# therma.net
KiCad netlist of a schematic drawn in EAGLE
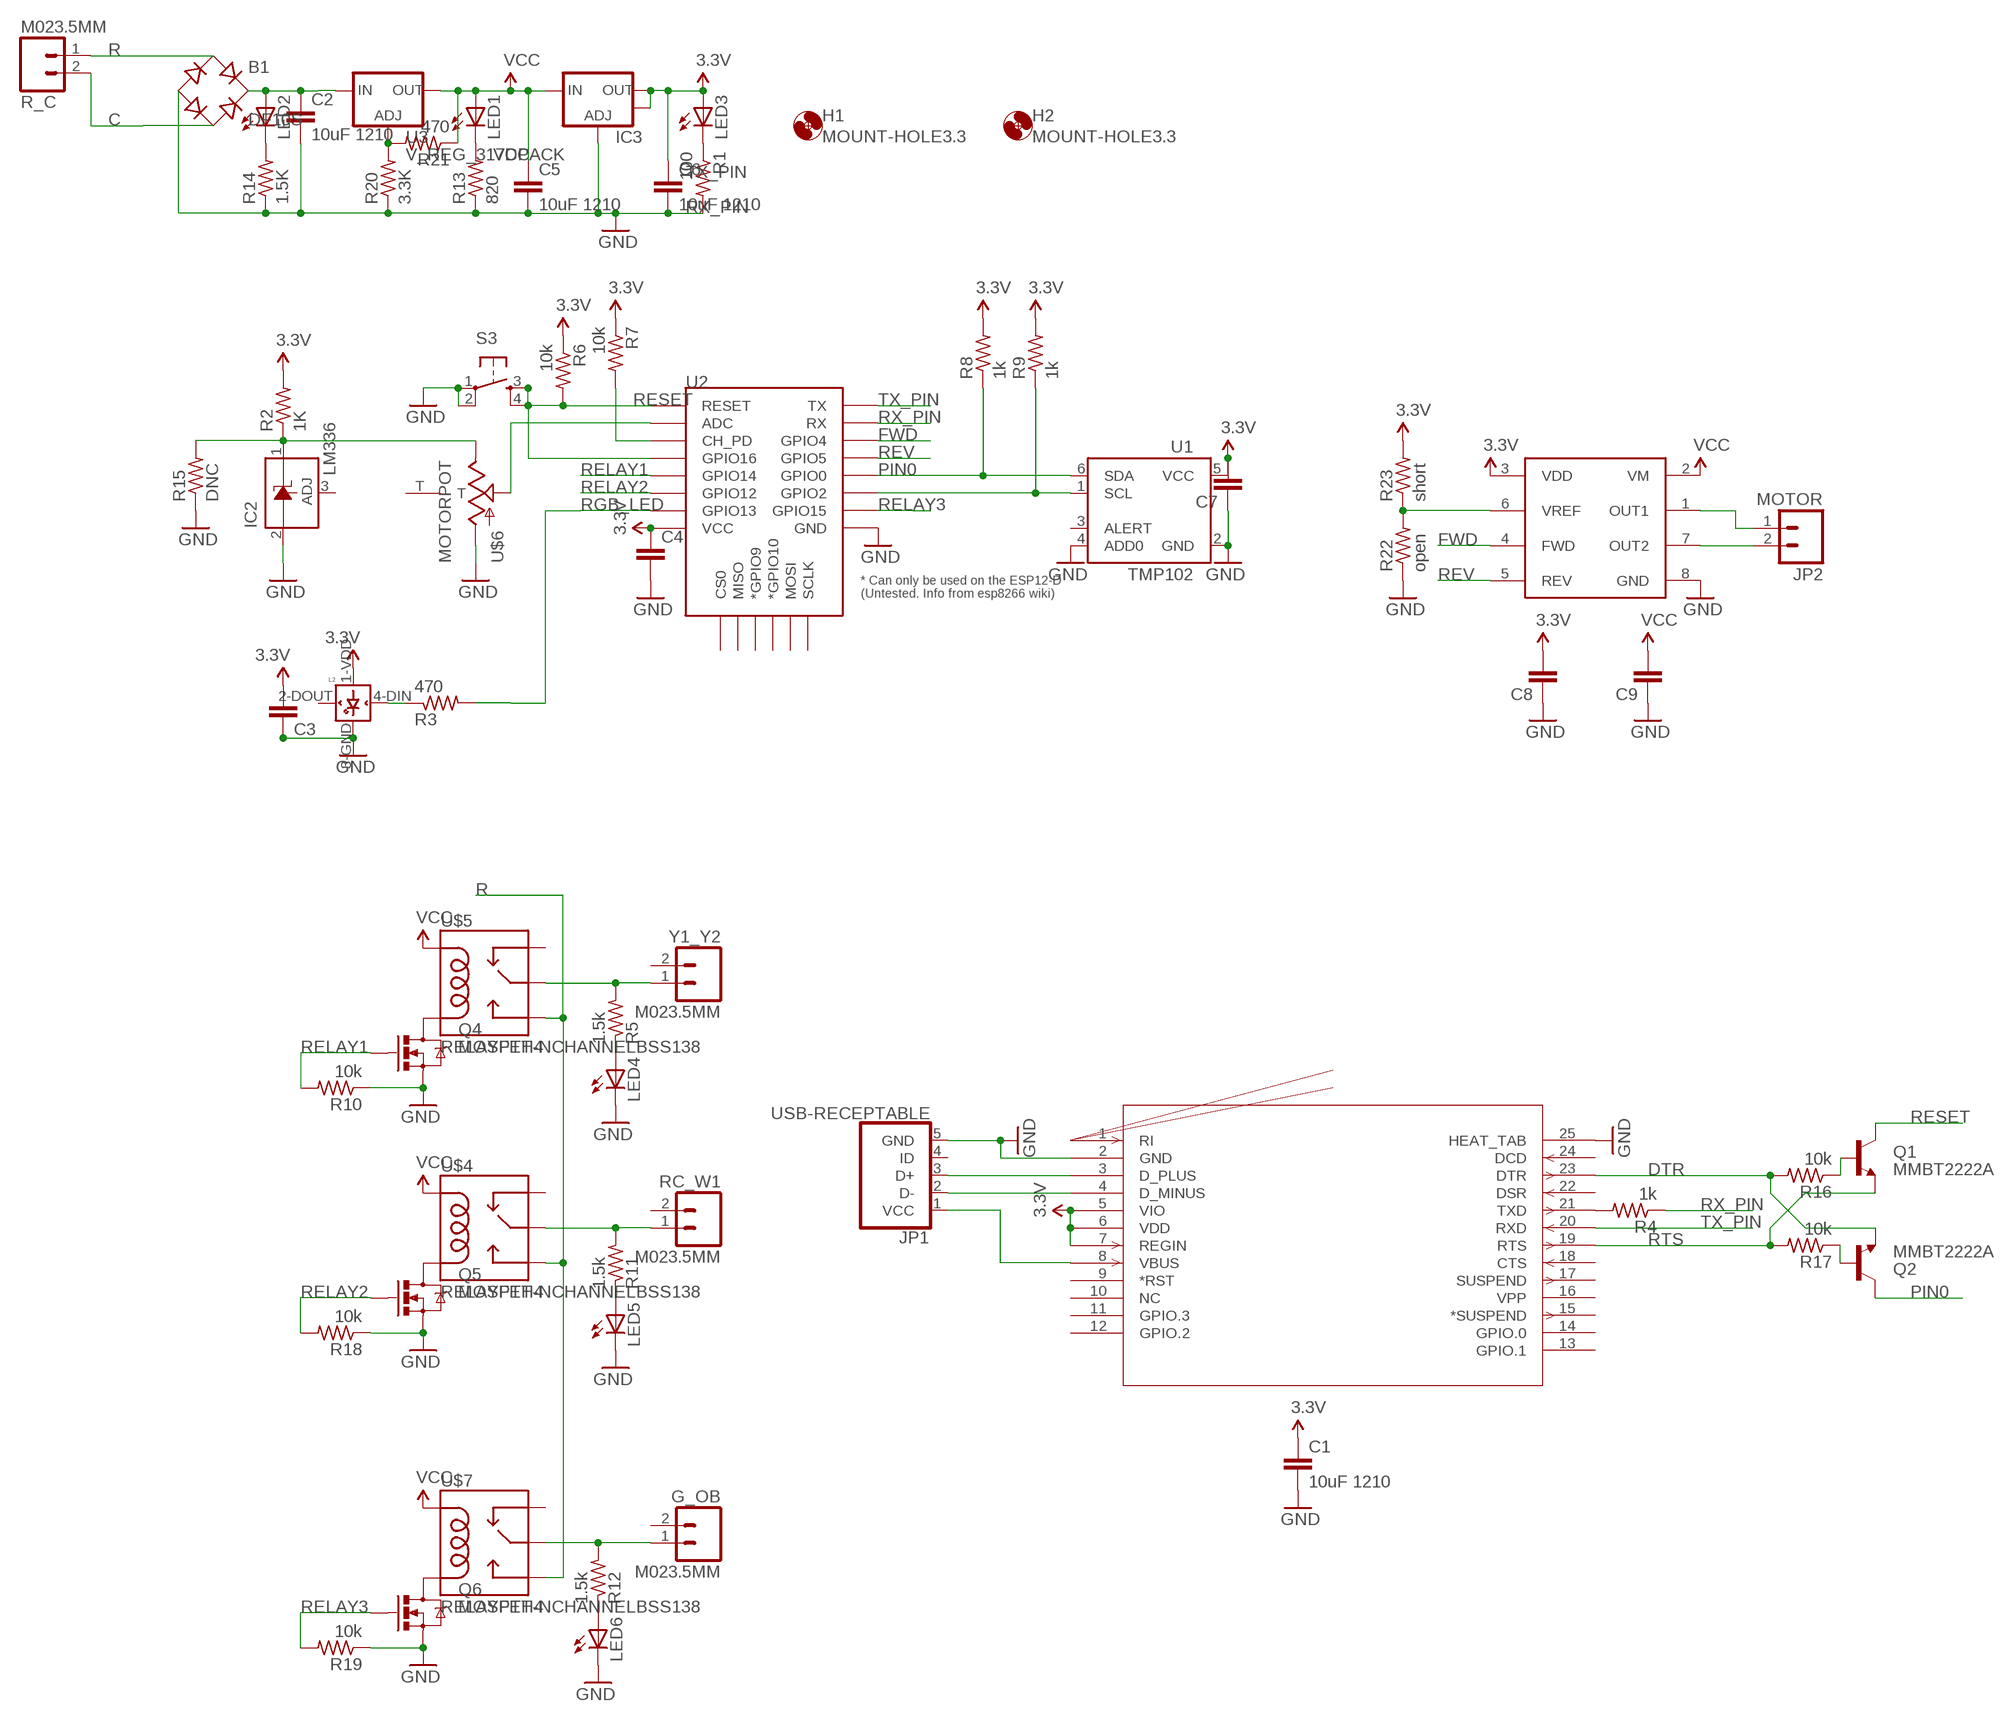
[diagram p0: schematic, sheet 1]

(export (version "E")
  (design (tool "Eeschema 10.0.6"))
  (components
    (comp (ref "B1")
      (value "DF10S")
      (footprint "eagle-import:DFS")
      (libsource (lib "eagle-import") (part "DFS10"))
    )
    (comp (ref "C1")
      (value "10uF 1210")
      (footprint "eagle-import:1210")
      (fields (field (name "PROD_ID") "CAP-09824"))
      (libsource (lib "eagle-import") (part "10UF50V20%(1210)"))
    )
    (comp (ref "C2")
      (value "10uF 1210")
      (footprint "eagle-import:1210")
      (fields (field (name "PROD_ID") "CAP-09824"))
      (libsource (lib "eagle-import") (part "10UF50V20%(1210)"))
    )
    (comp (ref "C3")
      (value "CAP0603-CAP")
      (footprint "eagle-import:0603-CAP")
      (libsource (lib "eagle-import") (part "CAP0603-CAP"))
    )
    (comp (ref "C4")
      (value "CAP0603-CAP")
      (footprint "eagle-import:0603-CAP")
      (libsource (lib "eagle-import") (part "CAP0603-CAP"))
    )
    (comp (ref "C5")
      (value "10uF 1210")
      (footprint "eagle-import:1210")
      (libsource (lib "eagle-import") (part "10UF50V20%(1210)"))
    )
    (comp (ref "C6")
      (value "10uF 1210")
      (footprint "eagle-import:1210")
      (fields (field (name "PROD_ID") "CAP-09824"))
      (libsource (lib "eagle-import") (part "10UF50V20%(1210)"))
    )
    (comp (ref "C7")
      (value "CAP0603-CAP")
      (footprint "eagle-import:0603-CAP")
      (libsource (lib "eagle-import") (part "CAP0603-CAP"))
    )
    (comp (ref "C8")
      (value "CAP0603-CAP")
      (footprint "eagle-import:0603-CAP")
      (libsource (lib "eagle-import") (part "CAP0603-CAP"))
    )
    (comp (ref "C9")
      (value "CAP0603-CAP")
      (footprint "eagle-import:0603-CAP")
      (libsource (lib "eagle-import") (part "CAP0603-CAP"))
    )
    (comp (ref "G_OB")
      (value "M023.5MM")
      (footprint "eagle-import:SCREWTERMINAL-3.5MM-2")
      (libsource (lib "eagle-import") (part "M023.5MM"))
    )
    (comp (ref "H1")
      (value "MOUNT-HOLE3.3")
      (footprint "eagle-import:3,3")
      (libsource (lib "eagle-import") (part "MOUNT-HOLE3.3"))
    )
    (comp (ref "H2")
      (value "MOUNT-HOLE3.3")
      (footprint "eagle-import:3,3")
      (libsource (lib "eagle-import") (part "MOUNT-HOLE3.3"))
    )
    (comp (ref "IC2")
      (value "LM336")
      (footprint "eagle-import:SOT23-3")
      (libsource (lib "eagle-import") (part "LM336"))
    )
    (comp (ref "IC3")
      (value "V_REG_LM1117SOT223")
      (footprint "eagle-import:SOT223")
      (libsource (lib "eagle-import") (part "V_REG_LM1117SOT223"))
    )
    (comp (ref "JP1")
      (value "USB-RECEPTABLE")
      (footprint "eagle-import:FCI-10103594-0001LF")
      (libsource (lib "eagle-import") (part "USB-RECEPTABLE"))
    )
    (comp (ref "JP2")
      (value "MOTOR")
      (footprint "eagle-import:1X02")
      (libsource (lib "eagle-import") (part "M02PTH"))
    )
    (comp (ref "L2")
      (value "WS2812B")
      (footprint "eagle-import:WS2812B")
      (libsource (lib "eagle-import") (part "WS2812B"))
    )
    (comp (ref "LED1")
      (value "LEDCHIPLED_1206")
      (footprint "eagle-import:CHIPLED_1206")
      (libsource (lib "eagle-import") (part "LEDCHIPLED_1206"))
    )
    (comp (ref "LED2")
      (value "LEDCHIPLED_1206")
      (footprint "eagle-import:CHIPLED_1206")
      (libsource (lib "eagle-import") (part "LEDCHIPLED_1206"))
    )
    (comp (ref "LED3")
      (value "LEDCHIPLED_1206")
      (footprint "eagle-import:CHIPLED_1206")
      (libsource (lib "eagle-import") (part "LEDCHIPLED_1206"))
    )
    (comp (ref "LED4")
      (value "LEDCHIPLED_1206")
      (footprint "eagle-import:CHIPLED_1206")
      (libsource (lib "eagle-import") (part "LEDCHIPLED_1206"))
    )
    (comp (ref "LED5")
      (value "LEDCHIPLED_1206")
      (footprint "eagle-import:CHIPLED_1206")
      (libsource (lib "eagle-import") (part "LEDCHIPLED_1206"))
    )
    (comp (ref "LED6")
      (value "LEDCHIPLED_1206")
      (footprint "eagle-import:CHIPLED_1206")
      (libsource (lib "eagle-import") (part "LEDCHIPLED_1206"))
    )
    (comp (ref "Q1")
      (value "MMBT2222A")
      (footprint "eagle-import:SOT23")
      (libsource (lib "eagle-import") (part "TRANSISTOR_NPNMMBT2222A"))
    )
    (comp (ref "Q2")
      (value "MMBT2222A")
      (footprint "eagle-import:SOT23")
      (libsource (lib "eagle-import") (part "TRANSISTOR_NPNMMBT2222A"))
    )
    (comp (ref "Q4")
      (value "MOSFET-NCHANNELBSS138")
      (footprint "eagle-import:SOT23")
      (libsource (lib "eagle-import") (part "MOSFET-NCHANNELBSS138"))
    )
    (comp (ref "Q5")
      (value "MOSFET-NCHANNELBSS138")
      (footprint "eagle-import:SOT23")
      (libsource (lib "eagle-import") (part "MOSFET-NCHANNELBSS138"))
    )
    (comp (ref "Q6")
      (value "MOSFET-NCHANNELBSS138")
      (footprint "eagle-import:SOT23")
      (libsource (lib "eagle-import") (part "MOSFET-NCHANNELBSS138"))
    )
    (comp (ref "R1")
      (value "100")
      (footprint "eagle-import:R0603")
      (libsource (lib "eagle-import") (part "R-US_R0603"))
    )
    (comp (ref "R2")
      (value "1K")
      (footprint "eagle-import:R0603")
      (libsource (lib "eagle-import") (part "R-US_R0603"))
    )
    (comp (ref "R3")
      (value "470")
      (footprint "eagle-import:R0603")
      (libsource (lib "eagle-import") (part "R-US_R0603"))
    )
    (comp (ref "R4")
      (value "1k")
      (footprint "eagle-import:R0603")
      (libsource (lib "eagle-import") (part "R-US_R0603"))
    )
    (comp (ref "R5")
      (value "1.5k")
      (footprint "eagle-import:R0603")
      (libsource (lib "eagle-import") (part "R-US_R0603"))
    )
    (comp (ref "R6")
      (value "10k")
      (footprint "eagle-import:R0603")
      (libsource (lib "eagle-import") (part "R-US_R0603"))
    )
    (comp (ref "R7")
      (value "10k")
      (footprint "eagle-import:R0603")
      (libsource (lib "eagle-import") (part "R-US_R0603"))
    )
    (comp (ref "R8")
      (value "1k")
      (footprint "eagle-import:R0603")
      (libsource (lib "eagle-import") (part "R-US_R0603"))
    )
    (comp (ref "R9")
      (value "1k")
      (footprint "eagle-import:R0603")
      (libsource (lib "eagle-import") (part "R-US_R0603"))
    )
    (comp (ref "R10")
      (value "10k")
      (footprint "eagle-import:R0603")
      (libsource (lib "eagle-import") (part "R-US_R0603"))
    )
    (comp (ref "R11")
      (value "1.5k")
      (footprint "eagle-import:R0603")
      (libsource (lib "eagle-import") (part "R-US_R0603"))
    )
    (comp (ref "R12")
      (value "1.5k")
      (footprint "eagle-import:R0603")
      (libsource (lib "eagle-import") (part "R-US_R0603"))
    )
    (comp (ref "R13")
      (value "820")
      (footprint "eagle-import:R0603")
      (libsource (lib "eagle-import") (part "R-US_R0603"))
    )
    (comp (ref "R14")
      (value "1.5K")
      (footprint "eagle-import:R0603")
      (libsource (lib "eagle-import") (part "R-US_R0603"))
    )
    (comp (ref "R15")
      (value "DNC")
      (footprint "eagle-import:R0603")
      (libsource (lib "eagle-import") (part "R-US_R0603"))
    )
    (comp (ref "R16")
      (value "10k")
      (footprint "eagle-import:R0603")
      (libsource (lib "eagle-import") (part "R-US_R0603"))
    )
    (comp (ref "R17")
      (value "10k")
      (footprint "eagle-import:R0603")
      (libsource (lib "eagle-import") (part "R-US_R0603"))
    )
    (comp (ref "R18")
      (value "10k")
      (footprint "eagle-import:R0603")
      (libsource (lib "eagle-import") (part "R-US_R0603"))
    )
    (comp (ref "R19")
      (value "10k")
      (footprint "eagle-import:R0603")
      (libsource (lib "eagle-import") (part "R-US_R0603"))
    )
    (comp (ref "R20")
      (value "3.3K")
      (footprint "eagle-import:R0603")
      (libsource (lib "eagle-import") (part "R-US_R0603"))
    )
    (comp (ref "R21")
      (value "470")
      (footprint "eagle-import:R0603")
      (libsource (lib "eagle-import") (part "R-US_R0603"))
    )
    (comp (ref "R22")
      (value "open")
      (footprint "eagle-import:R0603")
      (libsource (lib "eagle-import") (part "R-US_R0603"))
    )
    (comp (ref "R23")
      (value "short")
      (footprint "eagle-import:R0603")
      (libsource (lib "eagle-import") (part "R-US_R0603"))
    )
    (comp (ref "RC_W1")
      (value "M023.5MM")
      (footprint "eagle-import:SCREWTERMINAL-3.5MM-2")
      (libsource (lib "eagle-import") (part "M023.5MM"))
    )
    (comp (ref "R_C")
      (value "M023.5MM")
      (footprint "eagle-import:SCREWTERMINAL-3.5MM-2")
      (libsource (lib "eagle-import") (part "M023.5MM"))
    )
    (comp (ref "S3")
      (value "TAC_SWITCHSMD")
      (footprint "eagle-import:TACTILE_SWITCH_SMD")
      (libsource (lib "eagle-import") (part "TAC_SWITCHSMD"))
    )
    (comp (ref "U$1")
      (value "ZXBM5210SOIC")
      (footprint "eagle-import:SOIC8")
      (libsource (lib "eagle-import") (part "ZXBM5210SOIC"))
    )
    (comp (ref "U$4")
      (value "RELAYPTH4")
      (footprint "eagle-import:RELAY-JZC")
      (libsource (lib "eagle-import") (part "RELAYPTH4"))
    )
    (comp (ref "U$5")
      (value "RELAYPTH4")
      (footprint "eagle-import:RELAY-JZC")
      (libsource (lib "eagle-import") (part "RELAYPTH4"))
    )
    (comp (ref "U$6")
      (value "MOTORPOT")
      (footprint "eagle-import:MOTORIZEDPOT")
      (libsource (lib "eagle-import") (part "MOTORPOT"))
    )
    (comp (ref "U$7")
      (value "RELAYPTH4")
      (footprint "eagle-import:RELAY-JZC")
      (libsource (lib "eagle-import") (part "RELAYPTH4"))
    )
    (comp (ref "U$8")
      (value "CP2104-GM")
      (footprint "eagle-import:QFN24_4X4")
      (libsource (lib "eagle-import") (part "CP2104-GM"))
    )
    (comp (ref "U1")
      (value "TMP102")
      (footprint "eagle-import:SOT563")
      (libsource (lib "eagle-import") (part "TMP102"))
    )
    (comp (ref "U2")
      (value "ESP12ESMD")
      (footprint "eagle-import:ESP12E-SMD")
      (libsource (lib "eagle-import") (part "ESP12ESMD"))
    )
    (comp (ref "U3")
      (value "V_REG_317DPACK")
      (footprint "eagle-import:V-REG_DPACK")
      (libsource (lib "eagle-import") (part "V_REG_317DPACK"))
    )
    (comp (ref "Y1_Y2")
      (value "M023.5MM")
      (footprint "eagle-import:SCREWTERMINAL-3.5MM-2")
      (libsource (lib "eagle-import") (part "M023.5MM"))
    )
  )
  (nets
    (net (code "1") (name "/C") (class "Default")
      (node (ref "B1") (pin "AC2") (pinfunction "AC2_AC2") (pintype "passive"))
      (node (ref "R_C") (pin "2") (pinfunction "2_2") (pintype "passive"))
    )
    (net (code "2") (name "/DTR") (class "Default")
      (node (ref "Q2") (pin "2") (pinfunction "E_2") (pintype "passive"))
      (node (ref "R16") (pin "2") (pinfunction "2_2") (pintype "passive"))
      (node (ref "U$8") (pin "23") (pinfunction "DTR_23") (pintype "output"))
    )
    (net (code "3") (name "/FWD") (class "Default")
      (node (ref "U$1") (pin "4") (pinfunction "FWD_4") (pintype "bidirectional"))
      (node (ref "U2") (pin "GPIO4") (pinfunction "GPIO4_GPIO4") (pintype "bidirectional"))
    )
    (net (code "4") (name "/PIN0") (class "Default")
      (node (ref "Q2") (pin "3") (pinfunction "C_3") (pintype "passive"))
      (node (ref "R8") (pin "1") (pinfunction "1_1") (pintype "passive"))
      (node (ref "U1") (pin "6") (pinfunction "SDA_6") (pintype "bidirectional"))
      (node (ref "U2") (pin "GPIO0") (pinfunction "GPIO0_GPIO0") (pintype "bidirectional"))
    )
    (net (code "5") (name "/R") (class "Default")
      (node (ref "B1") (pin "AC1") (pinfunction "AC1_AC1") (pintype "passive"))
      (node (ref "R_C") (pin "1") (pinfunction "1_1") (pintype "passive"))
      (node (ref "U$4") (pin "3") (pinfunction "NO_3") (pintype "bidirectional"))
      (node (ref "U$5") (pin "3") (pinfunction "NO_3") (pintype "bidirectional"))
      (node (ref "U$7") (pin "3") (pinfunction "NO_3") (pintype "bidirectional"))
    )
    (net (code "6") (name "/RELAY1") (class "Default")
      (node (ref "Q4") (pin "1") (pinfunction "G_1") (pintype "passive"))
      (node (ref "R10") (pin "2") (pinfunction "2_2") (pintype "passive"))
      (node (ref "U2") (pin "GPIO14") (pinfunction "GPIO14_GPIO14") (pintype "bidirectional"))
    )
    (net (code "7") (name "/RELAY2") (class "Default")
      (node (ref "Q5") (pin "1") (pinfunction "G_1") (pintype "passive"))
      (node (ref "R18") (pin "2") (pinfunction "2_2") (pintype "passive"))
      (node (ref "U2") (pin "GPIO12") (pinfunction "GPIO12_GPIO12") (pintype "bidirectional"))
    )
    (net (code "8") (name "/RELAY3") (class "Default")
      (node (ref "Q6") (pin "1") (pinfunction "G_1") (pintype "passive"))
      (node (ref "R19") (pin "2") (pinfunction "2_2") (pintype "passive"))
      (node (ref "U2") (pin "GPIO15") (pinfunction "GPIO15_GPIO15") (pintype "bidirectional"))
    )
    (net (code "9") (name "/RESET") (class "Default")
      (node (ref "Q1") (pin "3") (pinfunction "C_3") (pintype "passive"))
      (node (ref "R6") (pin "2") (pinfunction "2_2") (pintype "passive"))
      (node (ref "S3") (pin "3") (pinfunction "3_3") (pintype "passive"))
      (node (ref "S3") (pin "4") (pinfunction "4_4") (pintype "passive"))
      (node (ref "U2") (pin "GPIO16") (pinfunction "GPIO16_GPIO16") (pintype "bidirectional"))
      (node (ref "U2") (pin "RESET") (pinfunction "RESET_RESET") (pintype "bidirectional"))
    )
    (net (code "10") (name "/REV") (class "Default")
      (node (ref "U$1") (pin "5") (pinfunction "REV_5") (pintype "bidirectional"))
      (node (ref "U2") (pin "GPIO5") (pinfunction "GPIO5_GPIO5") (pintype "bidirectional"))
    )
    (net (code "11") (name "/RGB_LED") (class "Default")
      (node (ref "R3") (pin "2") (pinfunction "2_2") (pintype "passive"))
      (node (ref "U2") (pin "GPIO13") (pinfunction "GPIO13_GPIO13") (pintype "bidirectional"))
    )
    (net (code "12") (name "/RTS") (class "Default")
      (node (ref "Q1") (pin "2") (pinfunction "E_2") (pintype "passive"))
      (node (ref "R17") (pin "2") (pinfunction "2_2") (pintype "passive"))
      (node (ref "U$8") (pin "19") (pinfunction "RTS_19") (pintype "output"))
    )
    (net (code "13") (name "/RX_PIN") (class "Default")
      (node (ref "R4") (pin "1") (pinfunction "1_1") (pintype "passive"))
      (node (ref "U2") (pin "RXD0") (pinfunction "RX_RXD0") (pintype "bidirectional"))
    )
    (net (code "14") (name "/TX_PIN") (class "Default")
      (node (ref "U$8") (pin "20") (pinfunction "RXD_20") (pintype "input"))
      (node (ref "U2") (pin "TXD0") (pinfunction "TX_TXD0") (pintype "bidirectional"))
    )
    (net (code "15") (name "3.3V") (class "Default")
      (node (ref "C1") (pin "1") (pinfunction "1_1") (pintype "passive"))
      (node (ref "C3") (pin "2") (pinfunction "2_2") (pintype "passive"))
      (node (ref "C4") (pin "1") (pinfunction "1_1") (pintype "passive"))
      (node (ref "C6") (pin "1") (pinfunction "1_1") (pintype "passive"))
      (node (ref "C7") (pin "2") (pinfunction "2_2") (pintype "passive"))
      (node (ref "C8") (pin "2") (pinfunction "2_2") (pintype "passive"))
      (node (ref "IC3") (pin "2") (pinfunction "OUT_2") (pintype "output"))
      (node (ref "IC3") (pin "4") (pinfunction "OUT_4") (pintype "output"))
      (node (ref "L2") (pin "1-VDD") (pinfunction "VDD_1-VDD") (pintype "bidirectional"))
      (node (ref "LED3") (pin "A") (pinfunction "A_A") (pintype "passive"))
      (node (ref "R2") (pin "2") (pinfunction "2_2") (pintype "passive"))
      (node (ref "R23") (pin "2") (pinfunction "2_2") (pintype "passive"))
      (node (ref "R6") (pin "1") (pinfunction "1_1") (pintype "passive"))
      (node (ref "R7") (pin "1") (pinfunction "1_1") (pintype "passive"))
      (node (ref "R8") (pin "2") (pinfunction "2_2") (pintype "passive"))
      (node (ref "R9") (pin "2") (pinfunction "2_2") (pintype "passive"))
      (node (ref "U$1") (pin "3") (pinfunction "VDD_3") (pintype "bidirectional"))
      (node (ref "U$8") (pin "5") (pinfunction "VIO_5") (pintype "power_in"))
      (node (ref "U$8") (pin "6") (pinfunction "VDD_6") (pintype "power_in"))
      (node (ref "U$8") (pin "7") (pinfunction "REGIN_7") (pintype "input"))
      (node (ref "U1") (pin "5") (pinfunction "VCC_5") (pintype "bidirectional"))
      (node (ref "U2") (pin "VCC") (pinfunction "VCC_VCC") (pintype "bidirectional"))
    )
    (net (code "16") (name "GND") (class "Default")
      (node (ref "B1") (pin "-") (pinfunction "-_-") (pintype "passive"))
      (node (ref "C1") (pin "2") (pinfunction "2_2") (pintype "passive"))
      (node (ref "C2") (pin "2") (pinfunction "2_2") (pintype "passive"))
      (node (ref "C3") (pin "1") (pinfunction "1_1") (pintype "passive"))
      (node (ref "C4") (pin "2") (pinfunction "2_2") (pintype "passive"))
      (node (ref "C5") (pin "2") (pinfunction "2_2") (pintype "passive"))
      (node (ref "C6") (pin "2") (pinfunction "2_2") (pintype "passive"))
      (node (ref "C7") (pin "1") (pinfunction "1_1") (pintype "passive"))
      (node (ref "C8") (pin "1") (pinfunction "1_1") (pintype "passive"))
      (node (ref "C9") (pin "1") (pinfunction "1_1") (pintype "passive"))
      (node (ref "IC2") (pin "2") (pinfunction "A_2") (pintype "input"))
      (node (ref "IC3") (pin "1") (pinfunction "ADJ_1") (pintype "input"))
      (node (ref "JP1") (pin "5") (pinfunction "GND_5") (pintype "bidirectional"))
      (node (ref "L2") (pin "3-GND") (pinfunction "GND_3-GND") (pintype "bidirectional"))
      (node (ref "LED4") (pin "C") (pinfunction "C_C") (pintype "passive"))
      (node (ref "LED5") (pin "C") (pinfunction "C_C") (pintype "passive"))
      (node (ref "LED6") (pin "C") (pinfunction "C_C") (pintype "passive"))
      (node (ref "Q4") (pin "2") (pinfunction "S_2") (pintype "passive"))
      (node (ref "Q5") (pin "2") (pinfunction "S_2") (pintype "passive"))
      (node (ref "Q6") (pin "2") (pinfunction "S_2") (pintype "passive"))
      (node (ref "R1") (pin "2") (pinfunction "2_2") (pintype "passive"))
      (node (ref "R10") (pin "1") (pinfunction "1_1") (pintype "passive"))
      (node (ref "R13") (pin "1") (pinfunction "1_1") (pintype "passive"))
      (node (ref "R14") (pin "1") (pinfunction "1_1") (pintype "passive"))
      (node (ref "R15") (pin "1") (pinfunction "1_1") (pintype "passive"))
      (node (ref "R18") (pin "1") (pinfunction "1_1") (pintype "passive"))
      (node (ref "R19") (pin "1") (pinfunction "1_1") (pintype "passive"))
      (node (ref "R20") (pin "1") (pinfunction "1_1") (pintype "passive"))
      (node (ref "R22") (pin "1") (pinfunction "1_1") (pintype "passive"))
      (node (ref "S3") (pin "1") (pinfunction "1_1") (pintype "passive"))
      (node (ref "S3") (pin "2") (pinfunction "2_2") (pintype "passive"))
      (node (ref "U$1") (pin "8") (pinfunction "GND_8") (pintype "bidirectional"))
      (node (ref "U$6") (pin "3'") (pinfunction "3_3'") (pintype "passive"))
      (node (ref "U$8") (pin "2") (pinfunction "GND_2") (pintype "power_in"))
      (node (ref "U$8") (pin "25") (pinfunction "HEAT_TAB_25") (pintype "passive"))
      (node (ref "U1") (pin "2") (pinfunction "GND_2") (pintype "bidirectional"))
      (node (ref "U1") (pin "4") (pinfunction "ADD0_4") (pintype "bidirectional"))
      (node (ref "U2") (pin "GND") (pinfunction "GND_GND") (pintype "bidirectional"))
    )
    (net (code "17") (name "Net-(IC2-C)") (class "Default")
      (node (ref "IC2") (pin "1") (pinfunction "C_1") (pintype "passive"))
      (node (ref "R15") (pin "2") (pinfunction "2_2") (pintype "passive"))
      (node (ref "R2") (pin "1") (pinfunction "1_1") (pintype "passive"))
      (node (ref "U$6") (pin "1'") (pinfunction "1_1'") (pintype "passive"))
    )
    (net (code "18") (name "Net-(JP1-D+)") (class "Default")
      (node (ref "JP1") (pin "3") (pinfunction "D+_3") (pintype "bidirectional"))
      (node (ref "U$8") (pin "3") (pinfunction "D_PLUS_3") (pintype "passive"))
    )
    (net (code "19") (name "Net-(JP1-D-)") (class "Default")
      (node (ref "JP1") (pin "2") (pinfunction "D-_2") (pintype "bidirectional"))
      (node (ref "U$8") (pin "4") (pinfunction "D_MINUS_4") (pintype "passive"))
    )
    (net (code "20") (name "Net-(JP1-VCC)") (class "Default")
      (node (ref "JP1") (pin "1") (pinfunction "VCC_1") (pintype "bidirectional"))
      (node (ref "U$8") (pin "8") (pinfunction "VBUS_8") (pintype "input"))
    )
    (net (code "21") (name "Net-(L2-DIN)") (class "Default")
      (node (ref "L2") (pin "4-DIN") (pinfunction "DIN_4-DIN") (pintype "input"))
      (node (ref "R3") (pin "1") (pinfunction "1_1") (pintype "passive"))
    )
    (net (code "22") (name "Net-(LED1-PadC)") (class "Default")
      (node (ref "LED1") (pin "C") (pinfunction "C_C") (pintype "passive"))
      (node (ref "R13") (pin "2") (pinfunction "2_2") (pintype "passive"))
    )
    (net (code "23") (name "Net-(LED2-PadC)") (class "Default")
      (node (ref "LED2") (pin "C") (pinfunction "C_C") (pintype "passive"))
      (node (ref "R14") (pin "2") (pinfunction "2_2") (pintype "passive"))
    )
    (net (code "24") (name "Net-(LED3-PadC)") (class "Default")
      (node (ref "LED3") (pin "C") (pinfunction "C_C") (pintype "passive"))
      (node (ref "R1") (pin "1") (pinfunction "1_1") (pintype "passive"))
    )
    (net (code "25") (name "Net-(LED4-PadA)") (class "Default")
      (node (ref "LED4") (pin "A") (pinfunction "A_A") (pintype "passive"))
      (node (ref "R5") (pin "1") (pinfunction "1_1") (pintype "passive"))
    )
    (net (code "26") (name "Net-(LED5-PadA)") (class "Default")
      (node (ref "LED5") (pin "A") (pinfunction "A_A") (pintype "passive"))
      (node (ref "R11") (pin "1") (pinfunction "1_1") (pintype "passive"))
    )
    (net (code "27") (name "Net-(LED6-PadA)") (class "Default")
      (node (ref "LED6") (pin "A") (pinfunction "A_A") (pintype "passive"))
      (node (ref "R12") (pin "1") (pinfunction "1_1") (pintype "passive"))
    )
    (net (code "28") (name "Net-(Q1-B)") (class "Default")
      (node (ref "Q1") (pin "1") (pinfunction "B_1") (pintype "passive"))
      (node (ref "R16") (pin "1") (pinfunction "1_1") (pintype "passive"))
    )
    (net (code "29") (name "Net-(Q2-B)") (class "Default")
      (node (ref "Q2") (pin "1") (pinfunction "B_1") (pintype "passive"))
      (node (ref "R17") (pin "1") (pinfunction "1_1") (pintype "passive"))
    )
    (net (code "30") (name "Net-(Q4-D)") (class "Default")
      (node (ref "Q4") (pin "3") (pinfunction "D_3") (pintype "passive"))
      (node (ref "U$5") (pin "1") (pinfunction "COIL2_1") (pintype "bidirectional"))
    )
    (net (code "31") (name "Net-(Q5-D)") (class "Default")
      (node (ref "Q5") (pin "3") (pinfunction "D_3") (pintype "passive"))
      (node (ref "U$4") (pin "1") (pinfunction "COIL2_1") (pintype "bidirectional"))
    )
    (net (code "32") (name "Net-(Q6-D)") (class "Default")
      (node (ref "Q6") (pin "3") (pinfunction "D_3") (pintype "passive"))
      (node (ref "U$7") (pin "1") (pinfunction "COIL2_1") (pintype "bidirectional"))
    )
    (net (code "33") (name "Net-(R7-Pad2)") (class "Default")
      (node (ref "R7") (pin "2") (pinfunction "2_2") (pintype "passive"))
      (node (ref "U2") (pin "CH_PD") (pinfunction "CH_PD_CH_PD") (pintype "bidirectional"))
    )
    (net (code "34") (name "Net-(U$1-OUT1)") (class "Default")
      (node (ref "JP2") (pin "1") (pinfunction "1_1") (pintype "passive"))
      (node (ref "U$1") (pin "1") (pinfunction "OUT1_1") (pintype "bidirectional"))
    )
    (net (code "35") (name "Net-(U$1-OUT2)") (class "Default")
      (node (ref "JP2") (pin "2") (pinfunction "2_2") (pintype "passive"))
      (node (ref "U$1") (pin "7") (pinfunction "OUT2_7") (pintype "bidirectional"))
    )
    (net (code "36") (name "Net-(U$1-VREF)") (class "Default")
      (node (ref "R22") (pin "2") (pinfunction "2_2") (pintype "passive"))
      (node (ref "R23") (pin "1") (pinfunction "1_1") (pintype "passive"))
      (node (ref "U$1") (pin "6") (pinfunction "VREF_6") (pintype "bidirectional"))
    )
    (net (code "37") (name "Net-(U$4-MAIN)") (class "Default")
      (node (ref "R11") (pin "2") (pinfunction "2_2") (pintype "passive"))
      (node (ref "RC_W1") (pin "1") (pinfunction "1_1") (pintype "passive"))
      (node (ref "U$4") (pin "4") (pinfunction "MAIN_4") (pintype "bidirectional"))
    )
    (net (code "38") (name "Net-(U$5-MAIN)") (class "Default")
      (node (ref "R5") (pin "2") (pinfunction "2_2") (pintype "passive"))
      (node (ref "U$5") (pin "4") (pinfunction "MAIN_4") (pintype "bidirectional"))
      (node (ref "Y1_Y2") (pin "1") (pinfunction "1_1") (pintype "passive"))
    )
    (net (code "39") (name "Net-(U$6-2)") (class "Default")
      (node (ref "U$6") (pin "2'") (pinfunction "2_2'") (pintype "passive"))
      (node (ref "U2") (pin "ADC") (pinfunction "ADC_ADC") (pintype "bidirectional"))
    )
    (net (code "40") (name "Net-(U$7-MAIN)") (class "Default")
      (node (ref "G_OB") (pin "1") (pinfunction "1_1") (pintype "passive"))
      (node (ref "R12") (pin "2") (pinfunction "2_2") (pintype "passive"))
      (node (ref "U$7") (pin "4") (pinfunction "MAIN_4") (pintype "bidirectional"))
    )
    (net (code "41") (name "Net-(U$8-TXD)") (class "Default")
      (node (ref "R4") (pin "2") (pinfunction "2_2") (pintype "passive"))
      (node (ref "U$8") (pin "21") (pinfunction "TXD_21") (pintype "output"))
    )
    (net (code "42") (name "Net-(U1-SCL)") (class "Default")
      (node (ref "R9") (pin "1") (pinfunction "1_1") (pintype "passive"))
      (node (ref "U1") (pin "1") (pinfunction "SCL_1") (pintype "bidirectional"))
      (node (ref "U2") (pin "GPIO2") (pinfunction "GPIO2_GPIO2") (pintype "bidirectional"))
    )
    (net (code "43") (name "Net-(U3-ADJ)") (class "Default")
      (node (ref "R20") (pin "2") (pinfunction "2_2") (pintype "passive"))
      (node (ref "R21") (pin "2") (pinfunction "2_2") (pintype "passive"))
      (node (ref "U3") (pin "1") (pinfunction "ADJ_1") (pintype "input"))
    )
    (net (code "44") (name "Net-(U3-IN)") (class "Default")
      (node (ref "B1") (pin "+") (pinfunction "+_+") (pintype "passive"))
      (node (ref "C2") (pin "1") (pinfunction "1_1") (pintype "passive"))
      (node (ref "LED2") (pin "A") (pinfunction "A_A") (pintype "passive"))
      (node (ref "U3") (pin "3") (pinfunction "IN_3") (pintype "input"))
    )
    (net (code "45") (name "VCC") (class "Default")
      (node (ref "C5") (pin "1") (pinfunction "1_1") (pintype "passive"))
      (node (ref "C9") (pin "2") (pinfunction "2_2") (pintype "passive"))
      (node (ref "IC3") (pin "3") (pinfunction "IN_3") (pintype "input"))
      (node (ref "LED1") (pin "A") (pinfunction "A_A") (pintype "passive"))
      (node (ref "R21") (pin "1") (pinfunction "1_1") (pintype "passive"))
      (node (ref "U$1") (pin "2") (pinfunction "VM_2") (pintype "bidirectional"))
      (node (ref "U$4") (pin "5") (pinfunction "COIL1_5") (pintype "bidirectional"))
      (node (ref "U$5") (pin "5") (pinfunction "COIL1_5") (pintype "bidirectional"))
      (node (ref "U$7") (pin "5") (pinfunction "COIL1_5") (pintype "bidirectional"))
      (node (ref "U3") (pin "4") (pinfunction "OUT_4") (pintype "output"))
    )
    (net (code "46") (name "unconnected-(G_OB-Pad2)") (class "Default")
      (node (ref "G_OB") (pin "2") (pinfunction "2_2") (pintype "passive"))
    )
    (net (code "47") (name "unconnected-(IC2-ADJ-Pad3)") (class "Default")
      (node (ref "IC2") (pin "3") (pinfunction "ADJ_3") (pintype "input"))
    )
    (net (code "48") (name "unconnected-(JP1-ID-Pad4)") (class "Default")
      (node (ref "JP1") (pin "4") (pinfunction "ID_4") (pintype "bidirectional"))
    )
    (net (code "49") (name "unconnected-(L2-DOUT-Pad2-DOUT)") (class "Default")
      (node (ref "L2") (pin "2-DOUT") (pinfunction "DOUT_2-DOUT") (pintype "output"))
    )
    (net (code "50") (name "unconnected-(RC_W1-Pad2)") (class "Default")
      (node (ref "RC_W1") (pin "2") (pinfunction "2_2") (pintype "passive"))
    )
    (net (code "51") (name "unconnected-(U$4-NC-Pad2)") (class "Default")
      (node (ref "U$4") (pin "2") (pinfunction "NC_2") (pintype "bidirectional"))
    )
    (net (code "52") (name "unconnected-(U$5-NC-Pad2)") (class "Default")
      (node (ref "U$5") (pin "2") (pinfunction "NC_2") (pintype "bidirectional"))
    )
    (net (code "53") (name "unconnected-(U$6-PadT)") (class "Default")
      (node (ref "U$6") (pin "T") (pinfunction "T_T") (pintype "bidirectional"))
    )
    (net (code "54") (name "unconnected-(U$7-NC-Pad2)") (class "Default")
      (node (ref "U$7") (pin "2") (pinfunction "NC_2") (pintype "bidirectional"))
    )
    (net (code "55") (name "unconnected-(U$8-*RST-Pad9)") (class "Default")
      (node (ref "U$8") (pin "9") (pinfunction "*RST_9") (pintype "passive"))
    )
    (net (code "56") (name "unconnected-(U$8-*SUSPEND-Pad15)") (class "Default")
      (node (ref "U$8") (pin "15") (pinfunction "*SUSPEND_15") (pintype "output"))
    )
    (net (code "57") (name "unconnected-(U$8-CTS-Pad18)") (class "Default")
      (node (ref "U$8") (pin "18") (pinfunction "CTS_18") (pintype "input"))
    )
    (net (code "58") (name "unconnected-(U$8-DCD-Pad24)") (class "Default")
      (node (ref "U$8") (pin "24") (pinfunction "DCD_24") (pintype "input"))
    )
    (net (code "59") (name "unconnected-(U$8-DSR-Pad22)") (class "Default")
      (node (ref "U$8") (pin "22") (pinfunction "DSR_22") (pintype "input"))
    )
    (net (code "60") (name "unconnected-(U$8-GPIO.0-Pad14)") (class "Default")
      (node (ref "U$8") (pin "14") (pinfunction "GPIO.0_14") (pintype "passive"))
    )
    (net (code "61") (name "unconnected-(U$8-GPIO.1-Pad13)") (class "Default")
      (node (ref "U$8") (pin "13") (pinfunction "GPIO.1_13") (pintype "passive"))
    )
    (net (code "62") (name "unconnected-(U$8-GPIO.2-Pad12)") (class "Default")
      (node (ref "U$8") (pin "12") (pinfunction "GPIO.2_12") (pintype "passive"))
    )
    (net (code "63") (name "unconnected-(U$8-GPIO.3-Pad11)") (class "Default")
      (node (ref "U$8") (pin "11") (pinfunction "GPIO.3_11") (pintype "passive"))
    )
    (net (code "64") (name "unconnected-(U$8-NC-Pad10)") (class "Default")
      (node (ref "U$8") (pin "10") (pinfunction "NC_10") (pintype "no_connect"))
    )
    (net (code "65") (name "unconnected-(U$8-RI-Pad1)") (class "Default")
      (node (ref "U$8") (pin "1") (pinfunction "RI_1") (pintype "input"))
    )
    (net (code "66") (name "unconnected-(U$8-SUSPEND-Pad17)") (class "Default")
      (node (ref "U$8") (pin "17") (pinfunction "SUSPEND_17") (pintype "output"))
    )
    (net (code "67") (name "unconnected-(U$8-VPP-Pad16)") (class "Default")
      (node (ref "U$8") (pin "16") (pinfunction "VPP_16") (pintype "passive"))
    )
    (net (code "68") (name "unconnected-(U1-ALERT-Pad3)") (class "Default")
      (node (ref "U1") (pin "3") (pinfunction "ALERT_3") (pintype "bidirectional"))
    )
    (net (code "69") (name "unconnected-(U2-*GPIO9-PadGPIO9)") (class "Default")
      (node (ref "U2") (pin "GPIO9") (pinfunction "*GPIO9_GPIO9") (pintype "bidirectional"))
    )
    (net (code "70") (name "unconnected-(U2-*GPIO10-PadGPIO10)") (class "Default")
      (node (ref "U2") (pin "GPIO10") (pinfunction "*GPIO10_GPIO10") (pintype "bidirectional"))
    )
    (net (code "71") (name "unconnected-(U2-PadCS0)") (class "Default")
      (node (ref "U2") (pin "CS0") (pinfunction "CS0_CS0") (pintype "bidirectional"))
    )
    (net (code "72") (name "unconnected-(U2-PadMISO)") (class "Default")
      (node (ref "U2") (pin "MISO") (pinfunction "MISO_MISO") (pintype "bidirectional"))
    )
    (net (code "73") (name "unconnected-(U2-PadMOSI)") (class "Default")
      (node (ref "U2") (pin "MOSI") (pinfunction "MOSI_MOSI") (pintype "bidirectional"))
    )
    (net (code "74") (name "unconnected-(U2-PadSCLK)") (class "Default")
      (node (ref "U2") (pin "SCLK") (pinfunction "SCLK_SCLK") (pintype "bidirectional"))
    )
    (net (code "75") (name "unconnected-(Y1_Y2-Pad2)") (class "Default")
      (node (ref "Y1_Y2") (pin "2") (pinfunction "2_2") (pintype "passive"))
    )
  )
)
